# 01-POWER.net
KiCad netlist of a schematic drawn in Altium Designer
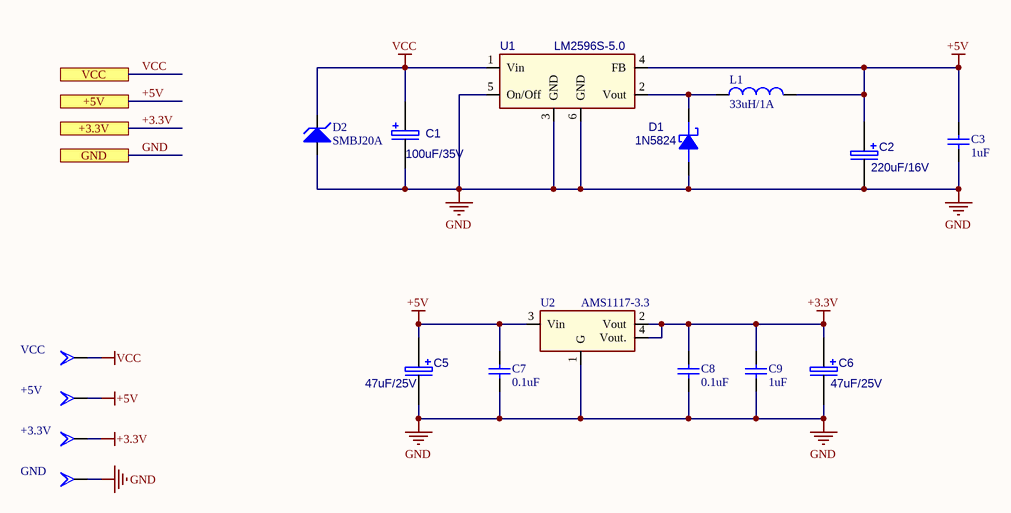
[diagram p0: 01-POWER.SchDoc]

(export (version "E")
  (design (tool "Eeschema 10.0.6"))
  (components
    (comp (ref "+3.3V")
      (value "T POINT A")
      (footprint "TP_60_30")
      (libsource (lib "EP_MCB_V6.0") (part "T POINT A"))
    )
    (comp (ref "+5V") (value "T POINT A") (libsource (lib "EP_MCB_V6.0") (part "T POINT A")))
    (comp (ref "C1")
      (value "100uF/35V")
      (footprint "CE06150")
      (description "E-CAP")
      (libsource (lib "*") (part "ECAP"))
    )
    (comp (ref "C2")
      (value "220uF/16V")
      (footprint "CE06150 - W")
      (description "E-CAP")
      (libsource (lib "*") (part "ECAP"))
    )
    (comp (ref "C3")
      (value "1uF")
      (footprint "0805_C")
      (description "Capacitor")
      (fields (field (name "PUBLISHER") "Altium Limited"))
      (libsource (lib "EP_MCB_V3.00") (part "Cap Semi"))
    )
    (comp (ref "C5")
      (value "47uF/25V")
      (footprint "CE06150 - W")
      (description "E-CAP")
      (libsource (lib "*") (part "ECAP"))
    )
    (comp (ref "C6")
      (value "47uF/25V")
      (footprint "CE06150 - W")
      (description "E-CAP")
      (libsource (lib "*") (part "ECAP"))
    )
    (comp (ref "C7")
      (value "0.1uF")
      (footprint "0805_C")
      (description "Capacitor")
      (fields (field (name "PUBLISHER") "Altium Limited"))
      (libsource (lib "EM_SENSOR_V3.01") (part "Cap Semi_1"))
    )
    (comp (ref "C8")
      (value "0.1uF")
      (footprint "0805_C")
      (description "Capacitor")
      (fields (field (name "PUBLISHER") "Altium Limited"))
      (libsource (lib "EM_SENSOR_V3.01") (part "Cap Semi_1"))
    )
    (comp (ref "C9")
      (value "1uF")
      (footprint "0805_C")
      (description "Capacitor")
      (fields (field (name "PUBLISHER") "Altium Limited"))
      (libsource (lib "EM_SENSOR_V3.01") (part "Cap Semi_1"))
    )
    (comp (ref "D1") (value "1N5824") (libsource (lib "EP_MCB_V4.1") (part "DIODE SCHOTTKY")))
    (comp (ref "D2")
      (value "SMBJ20A")
      (footprint "SMB-DO-214AA_DIOM4436X24N")
      (description "TVS")
      (fields (field (name "PUBLISHER") "Altium Limited"))
      (libsource (lib "EP_MCB_V3.02") (part "D Zener"))
    )
    (comp (ref "GND")
      (value "T POINT A")
      (footprint "TP_60_30")
      (libsource (lib "EP_MCB_V6.0") (part "T POINT A"))
    )
    (comp (ref "L1")
      (value "33uH/1A")
      (footprint "SMD_S7-7-5")
      (description "Inductor")
      (fields (field (name "PUBLISHER") "Altium Limited"))
      (libsource (lib "EP_MCB_V4.1") (part "Inductor"))
    )
    (comp (ref "U1")
      (value "LM2596S-5.0")
      (footprint "TO-263-5")
      (libsource (lib "EP_MCB_V4.1") (part "LM2596T-5.0"))
    )
    (comp (ref "U2")
      (value "AMS1117-3.3")
      (footprint "SOT223")
      (libsource (lib "EM_SENSOR_V2.01") (part "AMS1117-3.3"))
    )
    (comp (ref "VCC") (value "T POINT A") (libsource (lib "EP_MCB_V6.0") (part "T POINT A")))
  )
  (nets
    (net (code "1") (name "+3.3V") (class "Default")
      (node (ref "+3.3V") (pin "1") (pinfunction "TP_1") (pintype "passive"))
      (node (ref "C6") (pin "1") (pinfunction "+_1") (pintype "passive"))
      (node (ref "C8") (pin "2") (pinfunction "2_2") (pintype "passive"))
      (node (ref "C9") (pin "2") (pinfunction "2_2") (pintype "passive"))
      (node (ref "U2") (pin "2") (pinfunction "Vout_2") (pintype "passive"))
      (node (ref "U2") (pin "4") (pinfunction "Vout._4") (pintype "passive"))
    )
    (net (code "2") (name "+5V") (class "Default")
      (node (ref "+5V") (pin "1") (pinfunction "TP_1") (pintype "passive"))
      (node (ref "C2") (pin "1") (pinfunction "+_1") (pintype "passive"))
      (node (ref "C3") (pin "2") (pinfunction "2_2") (pintype "passive"))
      (node (ref "C5") (pin "1") (pinfunction "+_1") (pintype "passive"))
      (node (ref "C7") (pin "2") (pinfunction "2_2") (pintype "passive"))
      (node (ref "L1") (pin "2") (pinfunction "2_2") (pintype "passive"))
      (node (ref "U1") (pin "4") (pinfunction "FB_4") (pintype "passive"))
      (node (ref "U2") (pin "3") (pinfunction "Vin_3") (pintype "passive"))
    )
    (net (code "3") (name "GND") (class "Default")
      (node (ref "C1") (pin "2") (pinfunction "-_2") (pintype "passive"))
      (node (ref "C2") (pin "2") (pinfunction "-_2") (pintype "passive"))
      (node (ref "C3") (pin "1") (pinfunction "1_1") (pintype "passive"))
      (node (ref "C5") (pin "2") (pinfunction "-_2") (pintype "passive"))
      (node (ref "C6") (pin "2") (pinfunction "-_2") (pintype "passive"))
      (node (ref "C7") (pin "1") (pinfunction "1_1") (pintype "passive"))
      (node (ref "C8") (pin "1") (pinfunction "1_1") (pintype "passive"))
      (node (ref "C9") (pin "1") (pinfunction "1_1") (pintype "passive"))
      (node (ref "D1") (pin "1") (pinfunction "ANODE_1") (pintype "passive"))
      (node (ref "D2") (pin "1") (pinfunction "A_1") (pintype "passive"))
      (node (ref "GND") (pin "1") (pinfunction "TP_1") (pintype "passive"))
      (node (ref "U1") (pin "3") (pinfunction "GND_3") (pintype "passive"))
      (node (ref "U1") (pin "5") (pinfunction "On/Off_5") (pintype "passive"))
      (node (ref "U1") (pin "6") (pinfunction "GND_6") (pintype "passive"))
      (node (ref "U2") (pin "1") (pinfunction "G_1") (pintype "passive"))
    )
    (net (code "4") (name "Net-(D1-CATHODE)") (class "Default")
      (node (ref "D1") (pin "2") (pinfunction "CATHODE_2") (pintype "passive"))
      (node (ref "L1") (pin "1") (pinfunction "1_1") (pintype "passive"))
      (node (ref "U1") (pin "2") (pinfunction "Vout_2") (pintype "passive"))
    )
    (net (code "5") (name "VCC") (class "Default")
      (node (ref "C1") (pin "1") (pinfunction "+_1") (pintype "passive"))
      (node (ref "D2") (pin "2") (pinfunction "K_2") (pintype "passive"))
      (node (ref "U1") (pin "1") (pinfunction "Vin_1") (pintype "passive"))
      (node (ref "VCC") (pin "1") (pinfunction "TP_1") (pintype "passive"))
    )
  )
)
